# xbee_controller.net
KiCad netlist of a schematic drawn in EAGLE
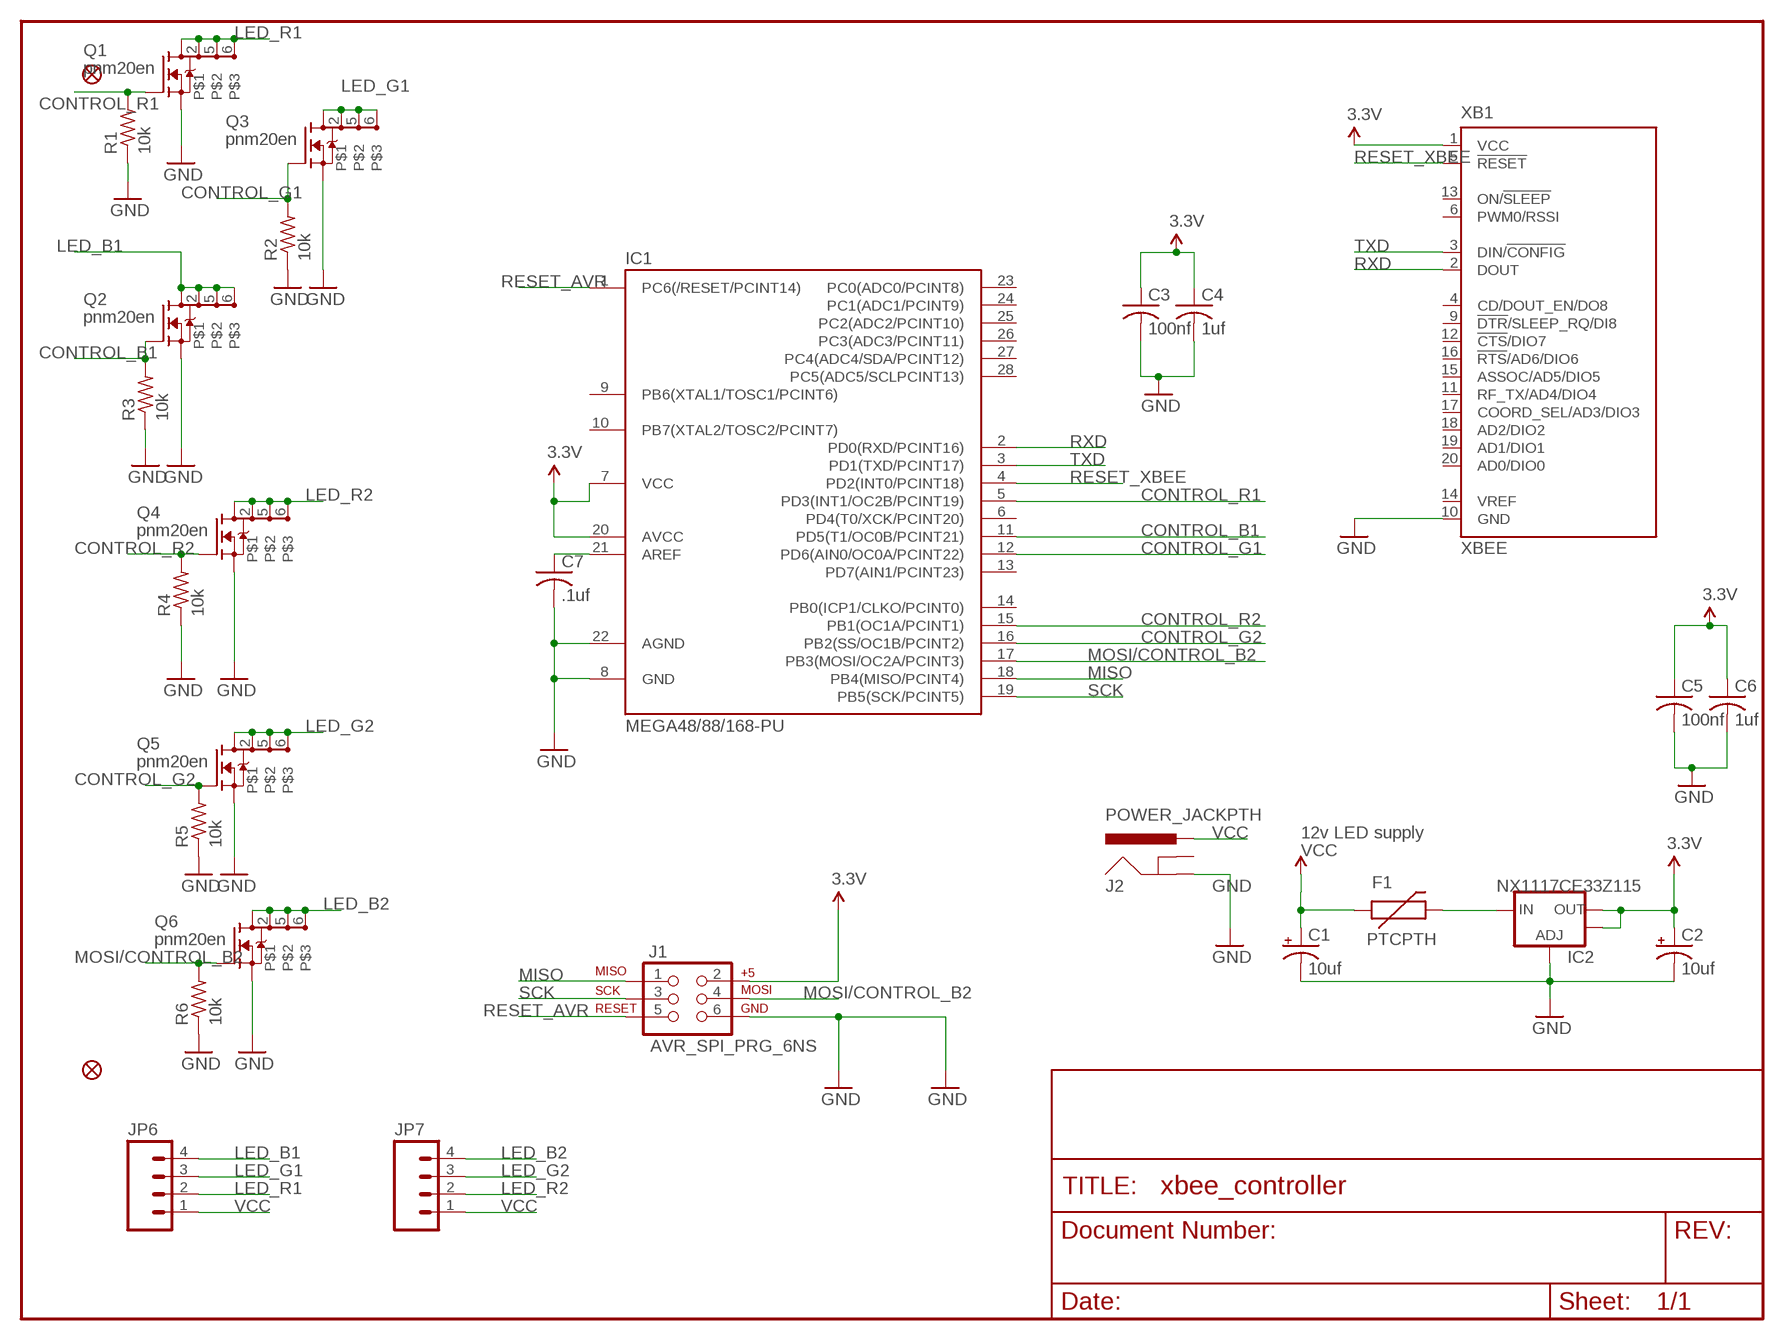
[diagram p0: schematic, sheet 1]

(export (version "E")
  (design (tool "Eeschema 10.0.6"))
  (components
    (comp (ref "C1")
      (value "10uf")
      (footprint "eagle-import:PANASONIC_A")
      (libsource (lib "eagle-import") (part "CPOL-USA"))
    )
    (comp (ref "C2")
      (value "10uf")
      (footprint "eagle-import:PANASONIC_A")
      (libsource (lib "eagle-import") (part "CPOL-USA"))
    )
    (comp (ref "C3")
      (value "100nf")
      (footprint "eagle-import:C0603")
      (libsource (lib "eagle-import") (part "C-USC0603"))
    )
    (comp (ref "C4")
      (value "1uf")
      (footprint "eagle-import:C0603")
      (libsource (lib "eagle-import") (part "C-USC0603"))
    )
    (comp (ref "C5")
      (value "100nf")
      (footprint "eagle-import:C0603")
      (libsource (lib "eagle-import") (part "C-USC0603"))
    )
    (comp (ref "C6")
      (value "1uf")
      (footprint "eagle-import:C0603")
      (libsource (lib "eagle-import") (part "C-USC0603"))
    )
    (comp (ref "C7")
      (value ".1uf")
      (footprint "eagle-import:C0603")
      (libsource (lib "eagle-import") (part "C-USC0603"))
    )
    (comp (ref "F1")
      (value "PTCPTH")
      (footprint "eagle-import:PTC")
      (libsource (lib "eagle-import") (part "PTCPTH"))
    )
    (comp (ref "IC1")
      (value "MEGA48/88/168-PU")
      (footprint "eagle-import:DIL28-3")
      (libsource (lib "eagle-import") (part "MEGA48/88/168-PU"))
    )
    (comp (ref "IC2")
      (value "NX1117CE33Z115")
      (footprint "eagle-import:SOT223")
      (libsource (lib "eagle-import") (part "V_REG_LM1117SOT223"))
    )
    (comp (ref "J1")
      (value "AVR_SPI_PRG_6NS")
      (footprint "eagle-import:2X3-NS")
      (libsource (lib "eagle-import") (part "AVR_SPI_PRG_6NS"))
    )
    (comp (ref "J2")
      (value "POWER_JACKPTH")
      (footprint "eagle-import:POWER_JACK_PTH")
      (libsource (lib "eagle-import") (part "POWER_JACKPTH"))
    )
    (comp (ref "JP2")
      (value "FIDUCIAL1.5X3")
      (footprint "eagle-import:FIDUCIAL-1.5X3")
      (libsource (lib "eagle-import") (part "FIDUCIAL1.5X3"))
    )
    (comp (ref "JP5")
      (value "FIDUCIAL1.5X3")
      (footprint "eagle-import:FIDUCIAL-1.5X3")
      (libsource (lib "eagle-import") (part "FIDUCIAL1.5X3"))
    )
    (comp (ref "JP6")
      (value "M04SCREW")
      (footprint "eagle-import:SCREWTERMINAL-3.5MM-4")
      (libsource (lib "eagle-import") (part "M04SCREW"))
    )
    (comp (ref "JP7")
      (value "M04SCREW")
      (footprint "eagle-import:SCREWTERMINAL-3.5MM-4")
      (libsource (lib "eagle-import") (part "M04SCREW"))
    )
    (comp (ref "Q1")
      (value "pnm20en")
      (footprint "eagle-import:BCR405U")
      (libsource (lib "eagle-import") (part "PMN20EN"))
    )
    (comp (ref "Q2")
      (value "pnm20en")
      (footprint "eagle-import:BCR405U")
      (libsource (lib "eagle-import") (part "PMN20EN"))
    )
    (comp (ref "Q3")
      (value "pnm20en")
      (footprint "eagle-import:BCR405U")
      (libsource (lib "eagle-import") (part "PMN20EN"))
    )
    (comp (ref "Q4")
      (value "pnm20en")
      (footprint "eagle-import:BCR405U")
      (libsource (lib "eagle-import") (part "PMN20EN"))
    )
    (comp (ref "Q5")
      (value "pnm20en")
      (footprint "eagle-import:BCR405U")
      (libsource (lib "eagle-import") (part "PMN20EN"))
    )
    (comp (ref "Q6")
      (value "pnm20en")
      (footprint "eagle-import:BCR405U")
      (libsource (lib "eagle-import") (part "PMN20EN"))
    )
    (comp (ref "R1")
      (value "10k")
      (footprint "eagle-import:R0603")
      (libsource (lib "eagle-import") (part "R-US_R0603"))
    )
    (comp (ref "R2")
      (value "10k")
      (footprint "eagle-import:R0603")
      (libsource (lib "eagle-import") (part "R-US_R0603"))
    )
    (comp (ref "R3")
      (value "10k")
      (footprint "eagle-import:R0603")
      (libsource (lib "eagle-import") (part "R-US_R0603"))
    )
    (comp (ref "R4")
      (value "10k")
      (footprint "eagle-import:R0603")
      (libsource (lib "eagle-import") (part "R-US_R0603"))
    )
    (comp (ref "R5")
      (value "10k")
      (footprint "eagle-import:R0603")
      (libsource (lib "eagle-import") (part "R-US_R0603"))
    )
    (comp (ref "R6")
      (value "10k")
      (footprint "eagle-import:R0603")
      (libsource (lib "eagle-import") (part "R-US_R0603"))
    )
    (comp (ref "XB1")
      (value "XBEE")
      (footprint "eagle-import:XBEE")
      (fields (field (name "MPN") "XBP24-Z7UIT-004"))
      (libsource (lib "eagle-import") (part "XBEE"))
    )
  )
  (nets
    (net (code "1") (name "/CONTROL_B1") (class "Default")
      (node (ref "IC1") (pin "11") (pinfunction "PD5(T1/OC0B/PCINT21)_11") (pintype "bidirectional"))
      (node (ref "Q2") (pin "3") (pinfunction "G_3") (pintype "passive"))
      (node (ref "R3") (pin "2") (pinfunction "2_2") (pintype "passive"))
    )
    (net (code "2") (name "/CONTROL_G1") (class "Default")
      (node (ref "IC1") (pin "12") (pinfunction "PD6(AIN0/OC0A/PCINT22)_12") (pintype "bidirectional"))
      (node (ref "Q3") (pin "3") (pinfunction "G_3") (pintype "passive"))
      (node (ref "R2") (pin "2") (pinfunction "2_2") (pintype "passive"))
    )
    (net (code "3") (name "/CONTROL_G2") (class "Default")
      (node (ref "IC1") (pin "16") (pinfunction "PB2(SS/OC1B/PCINT2)_16") (pintype "bidirectional"))
      (node (ref "Q5") (pin "3") (pinfunction "G_3") (pintype "passive"))
      (node (ref "R5") (pin "2") (pinfunction "2_2") (pintype "passive"))
    )
    (net (code "4") (name "/CONTROL_R1") (class "Default")
      (node (ref "IC1") (pin "5") (pinfunction "PD3(INT1/OC2B/PCINT19)_5") (pintype "bidirectional"))
      (node (ref "Q1") (pin "3") (pinfunction "G_3") (pintype "passive"))
      (node (ref "R1") (pin "2") (pinfunction "2_2") (pintype "passive"))
    )
    (net (code "5") (name "/CONTROL_R2") (class "Default")
      (node (ref "IC1") (pin "15") (pinfunction "PB1(OC1A/PCINT1)_15") (pintype "bidirectional"))
      (node (ref "Q4") (pin "3") (pinfunction "G_3") (pintype "passive"))
      (node (ref "R4") (pin "2") (pinfunction "2_2") (pintype "passive"))
    )
    (net (code "6") (name "/LED_B1") (class "Default")
      (node (ref "JP6") (pin "4") (pinfunction "4_4") (pintype "passive"))
      (node (ref "Q2") (pin "1") (pinfunction "D_1") (pintype "passive"))
      (node (ref "Q2") (pin "2") (pinfunction "P$1_2") (pintype "passive"))
      (node (ref "Q2") (pin "5") (pinfunction "P$2_5") (pintype "passive"))
      (node (ref "Q2") (pin "6") (pinfunction "P$3_6") (pintype "passive"))
    )
    (net (code "7") (name "/LED_B2") (class "Default")
      (node (ref "JP7") (pin "4") (pinfunction "4_4") (pintype "passive"))
      (node (ref "Q6") (pin "1") (pinfunction "D_1") (pintype "passive"))
      (node (ref "Q6") (pin "2") (pinfunction "P$1_2") (pintype "passive"))
      (node (ref "Q6") (pin "5") (pinfunction "P$2_5") (pintype "passive"))
      (node (ref "Q6") (pin "6") (pinfunction "P$3_6") (pintype "passive"))
    )
    (net (code "8") (name "/LED_G1") (class "Default")
      (node (ref "JP6") (pin "3") (pinfunction "3_3") (pintype "passive"))
      (node (ref "Q3") (pin "1") (pinfunction "D_1") (pintype "passive"))
      (node (ref "Q3") (pin "2") (pinfunction "P$1_2") (pintype "passive"))
      (node (ref "Q3") (pin "5") (pinfunction "P$2_5") (pintype "passive"))
      (node (ref "Q3") (pin "6") (pinfunction "P$3_6") (pintype "passive"))
    )
    (net (code "9") (name "/LED_G2") (class "Default")
      (node (ref "JP7") (pin "3") (pinfunction "3_3") (pintype "passive"))
      (node (ref "Q5") (pin "1") (pinfunction "D_1") (pintype "passive"))
      (node (ref "Q5") (pin "2") (pinfunction "P$1_2") (pintype "passive"))
      (node (ref "Q5") (pin "5") (pinfunction "P$2_5") (pintype "passive"))
      (node (ref "Q5") (pin "6") (pinfunction "P$3_6") (pintype "passive"))
    )
    (net (code "10") (name "/LED_R1") (class "Default")
      (node (ref "JP6") (pin "2") (pinfunction "2_2") (pintype "passive"))
      (node (ref "Q1") (pin "1") (pinfunction "D_1") (pintype "passive"))
      (node (ref "Q1") (pin "2") (pinfunction "P$1_2") (pintype "passive"))
      (node (ref "Q1") (pin "5") (pinfunction "P$2_5") (pintype "passive"))
      (node (ref "Q1") (pin "6") (pinfunction "P$3_6") (pintype "passive"))
    )
    (net (code "11") (name "/LED_R2") (class "Default")
      (node (ref "JP7") (pin "2") (pinfunction "2_2") (pintype "passive"))
      (node (ref "Q4") (pin "1") (pinfunction "D_1") (pintype "passive"))
      (node (ref "Q4") (pin "2") (pinfunction "P$1_2") (pintype "passive"))
      (node (ref "Q4") (pin "5") (pinfunction "P$2_5") (pintype "passive"))
      (node (ref "Q4") (pin "6") (pinfunction "P$3_6") (pintype "passive"))
    )
    (net (code "12") (name "/MISO") (class "Default")
      (node (ref "IC1") (pin "18") (pinfunction "PB4(MISO/PCINT4)_18") (pintype "bidirectional"))
      (node (ref "J1") (pin "1") (pinfunction "1_1") (pintype "passive"))
    )
    (net (code "13") (name "/MOSI{slash}CONTROL_B2") (class "Default")
      (node (ref "IC1") (pin "17") (pinfunction "PB3(MOSI/OC2A/PCINT3)_17") (pintype "bidirectional"))
      (node (ref "J1") (pin "4") (pinfunction "4_4") (pintype "passive"))
      (node (ref "Q6") (pin "3") (pinfunction "G_3") (pintype "passive"))
      (node (ref "R6") (pin "2") (pinfunction "2_2") (pintype "passive"))
    )
    (net (code "14") (name "/RESET_AVR") (class "Default")
      (node (ref "IC1") (pin "1") (pinfunction "PC6(/RESET/PCINT14)_1") (pintype "bidirectional"))
      (node (ref "J1") (pin "5") (pinfunction "5_5") (pintype "passive"))
    )
    (net (code "15") (name "/RESET_XBEE") (class "Default")
      (node (ref "IC1") (pin "4") (pinfunction "PD2(INT0/PCINT18)_4") (pintype "bidirectional"))
      (node (ref "XB1") (pin "5") (pinfunction "~{RESET}_5") (pintype "input"))
    )
    (net (code "16") (name "/RXD") (class "Default")
      (node (ref "IC1") (pin "2") (pinfunction "PD0(RXD/PCINT16)_2") (pintype "bidirectional"))
      (node (ref "XB1") (pin "2") (pinfunction "DOUT_2") (pintype "output"))
    )
    (net (code "17") (name "/SCK") (class "Default")
      (node (ref "IC1") (pin "19") (pinfunction "PB5(SCK/PCINT5)_19") (pintype "bidirectional"))
      (node (ref "J1") (pin "3") (pinfunction "3_3") (pintype "passive"))
    )
    (net (code "18") (name "/TXD") (class "Default")
      (node (ref "IC1") (pin "3") (pinfunction "PD1(TXD/PCINT17)_3") (pintype "bidirectional"))
      (node (ref "XB1") (pin "3") (pinfunction "DIN/~{CONFIG}_3") (pintype "input"))
    )
    (net (code "19") (name "3.3V") (class "Default")
      (node (ref "C2") (pin "+") (pinfunction "+_+") (pintype "passive"))
      (node (ref "C3") (pin "1") (pinfunction "1_1") (pintype "passive"))
      (node (ref "C4") (pin "1") (pinfunction "1_1") (pintype "passive"))
      (node (ref "C5") (pin "1") (pinfunction "1_1") (pintype "passive"))
      (node (ref "C6") (pin "1") (pinfunction "1_1") (pintype "passive"))
      (node (ref "IC1") (pin "20") (pinfunction "AVCC_20") (pintype "passive"))
      (node (ref "IC1") (pin "7") (pinfunction "VCC_7") (pintype "power_in"))
      (node (ref "IC2") (pin "2") (pinfunction "OUT_2") (pintype "output"))
      (node (ref "IC2") (pin "4") (pinfunction "OUT_4") (pintype "output"))
      (node (ref "J1") (pin "2") (pinfunction "2_2") (pintype "passive"))
      (node (ref "XB1") (pin "1") (pinfunction "VCC_1") (pintype "power_in"))
    )
    (net (code "20") (name "GND") (class "Default")
      (node (ref "C1") (pin "-") (pinfunction "-_-") (pintype "passive"))
      (node (ref "C2") (pin "-") (pinfunction "-_-") (pintype "passive"))
      (node (ref "C3") (pin "2") (pinfunction "2_2") (pintype "passive"))
      (node (ref "C4") (pin "2") (pinfunction "2_2") (pintype "passive"))
      (node (ref "C5") (pin "2") (pinfunction "2_2") (pintype "passive"))
      (node (ref "C6") (pin "2") (pinfunction "2_2") (pintype "passive"))
      (node (ref "C7") (pin "2") (pinfunction "2_2") (pintype "passive"))
      (node (ref "IC1") (pin "22") (pinfunction "AGND_22") (pintype "power_in"))
      (node (ref "IC1") (pin "8") (pinfunction "GND_8") (pintype "power_in"))
      (node (ref "IC2") (pin "1") (pinfunction "ADJ_1") (pintype "input"))
      (node (ref "J1") (pin "6") (pinfunction "6_6") (pintype "passive"))
      (node (ref "J2") (pin "GND") (pinfunction "GND_GND") (pintype "bidirectional"))
      (node (ref "Q1") (pin "4") (pinfunction "S_4") (pintype "passive"))
      (node (ref "Q2") (pin "4") (pinfunction "S_4") (pintype "passive"))
      (node (ref "Q3") (pin "4") (pinfunction "S_4") (pintype "passive"))
      (node (ref "Q4") (pin "4") (pinfunction "S_4") (pintype "passive"))
      (node (ref "Q5") (pin "4") (pinfunction "S_4") (pintype "passive"))
      (node (ref "Q6") (pin "4") (pinfunction "S_4") (pintype "passive"))
      (node (ref "R1") (pin "1") (pinfunction "1_1") (pintype "passive"))
      (node (ref "R2") (pin "1") (pinfunction "1_1") (pintype "passive"))
      (node (ref "R3") (pin "1") (pinfunction "1_1") (pintype "passive"))
      (node (ref "R4") (pin "1") (pinfunction "1_1") (pintype "passive"))
      (node (ref "R5") (pin "1") (pinfunction "1_1") (pintype "passive"))
      (node (ref "R6") (pin "1") (pinfunction "1_1") (pintype "passive"))
      (node (ref "XB1") (pin "10") (pinfunction "GND_10") (pintype "power_in"))
    )
    (net (code "21") (name "Net-(F1-2)") (class "Default")
      (node (ref "F1") (pin "P$2") (pinfunction "2_P$2") (pintype "bidirectional"))
      (node (ref "IC2") (pin "3") (pinfunction "IN_3") (pintype "input"))
    )
    (net (code "22") (name "Net-(IC1-AREF)") (class "Default")
      (node (ref "C7") (pin "1") (pinfunction "1_1") (pintype "passive"))
      (node (ref "IC1") (pin "21") (pinfunction "AREF_21") (pintype "passive"))
    )
    (net (code "23") (name "VCC") (class "Default")
      (node (ref "C1") (pin "+") (pinfunction "+_+") (pintype "passive"))
      (node (ref "F1") (pin "P$1") (pinfunction "1_P$1") (pintype "bidirectional"))
      (node (ref "J2") (pin "PWR") (pinfunction "PWR_PWR") (pintype "bidirectional"))
      (node (ref "JP6") (pin "1") (pinfunction "1_1") (pintype "passive"))
      (node (ref "JP7") (pin "1") (pinfunction "1_1") (pintype "passive"))
    )
    (net (code "24") (name "unconnected-(IC1-PB0(ICP1{slash}CLKO{slash}PCINT0)-Pad14)") (class "Default")
      (node (ref "IC1") (pin "14") (pinfunction "PB0(ICP1/CLKO/PCINT0)_14") (pintype "bidirectional"))
    )
    (net (code "25") (name "unconnected-(IC1-PB6(XTAL1{slash}TOSC1{slash}PCINT6)-Pad9)") (class "Default")
      (node (ref "IC1") (pin "9") (pinfunction "PB6(XTAL1/TOSC1/PCINT6)_9") (pintype "bidirectional"))
    )
    (net (code "26") (name "unconnected-(IC1-PB7(XTAL2{slash}TOSC2{slash}PCINT7)-Pad10)") (class "Default")
      (node (ref "IC1") (pin "10") (pinfunction "PB7(XTAL2/TOSC2/PCINT7)_10") (pintype "bidirectional"))
    )
    (net (code "27") (name "unconnected-(IC1-PC0(ADC0{slash}PCINT8)-Pad23)") (class "Default")
      (node (ref "IC1") (pin "23") (pinfunction "PC0(ADC0/PCINT8)_23") (pintype "bidirectional"))
    )
    (net (code "28") (name "unconnected-(IC1-PC1(ADC1{slash}PCINT9)-Pad24)") (class "Default")
      (node (ref "IC1") (pin "24") (pinfunction "PC1(ADC1/PCINT9)_24") (pintype "bidirectional"))
    )
    (net (code "29") (name "unconnected-(IC1-PC2(ADC2{slash}PCINT10)-Pad25)") (class "Default")
      (node (ref "IC1") (pin "25") (pinfunction "PC2(ADC2/PCINT10)_25") (pintype "bidirectional"))
    )
    (net (code "30") (name "unconnected-(IC1-PC3(ADC3{slash}PCINT11)-Pad26)") (class "Default")
      (node (ref "IC1") (pin "26") (pinfunction "PC3(ADC3/PCINT11)_26") (pintype "bidirectional"))
    )
    (net (code "31") (name "unconnected-(IC1-PC4(ADC4{slash}SDA{slash}PCINT12)-Pad27)") (class "Default")
      (node (ref "IC1") (pin "27") (pinfunction "PC4(ADC4/SDA/PCINT12)_27") (pintype "bidirectional"))
    )
    (net (code "32") (name "unconnected-(IC1-PC5(ADC5{slash}SCLPCINT13)-Pad28)") (class "Default")
      (node (ref "IC1") (pin "28") (pinfunction "PC5(ADC5/SCLPCINT13)_28") (pintype "bidirectional"))
    )
    (net (code "33") (name "unconnected-(IC1-PD4(T0{slash}XCK{slash}PCINT20)-Pad6)") (class "Default")
      (node (ref "IC1") (pin "6") (pinfunction "PD4(T0/XCK/PCINT20)_6") (pintype "bidirectional"))
    )
    (net (code "34") (name "unconnected-(IC1-PD7(AIN1{slash}PCINT23)-Pad13)") (class "Default")
      (node (ref "IC1") (pin "13") (pinfunction "PD7(AIN1/PCINT23)_13") (pintype "bidirectional"))
    )
    (net (code "35") (name "unconnected-(J2-PadGNDBREAK)") (class "Default")
      (node (ref "J2") (pin "GNDBREAK") (pinfunction "GNDBREAK_GNDBREAK") (pintype "bidirectional"))
    )
    (net (code "36") (name "unconnected-(XB1-AD0{slash}DIO0-Pad20)") (class "Default")
      (node (ref "XB1") (pin "20") (pinfunction "AD0/DIO0_20") (pintype "bidirectional"))
    )
    (net (code "37") (name "unconnected-(XB1-AD1{slash}DIO1-Pad19)") (class "Default")
      (node (ref "XB1") (pin "19") (pinfunction "AD1/DIO1_19") (pintype "bidirectional"))
    )
    (net (code "38") (name "unconnected-(XB1-AD2{slash}DIO2-Pad18)") (class "Default")
      (node (ref "XB1") (pin "18") (pinfunction "AD2/DIO2_18") (pintype "bidirectional"))
    )
    (net (code "39") (name "unconnected-(XB1-ASSOC{slash}AD5{slash}DIO5-Pad15)") (class "Default")
      (node (ref "XB1") (pin "15") (pinfunction "ASSOC/AD5/DIO5_15") (pintype "bidirectional"))
    )
    (net (code "40") (name "unconnected-(XB1-CD{slash}DOUT_EN{slash}DO8-Pad4)") (class "Default")
      (node (ref "XB1") (pin "4") (pinfunction "CD/DOUT_EN/DO8_4") (pintype "output"))
    )
    (net (code "41") (name "unconnected-(XB1-COORD_SEL{slash}AD3{slash}DIO3-Pad17)") (class "Default")
      (node (ref "XB1") (pin "17") (pinfunction "COORD_SEL/AD3/DIO3_17") (pintype "bidirectional"))
    )
    (net (code "42") (name "unconnected-(XB1-ON{slash}~{SLEEP}-Pad13)") (class "Default")
      (node (ref "XB1") (pin "13") (pinfunction "ON/~{SLEEP}_13") (pintype "output"))
    )
    (net (code "43") (name "unconnected-(XB1-PWM0{slash}RSSI-Pad6)") (class "Default")
      (node (ref "XB1") (pin "6") (pinfunction "PWM0/RSSI_6") (pintype "output"))
    )
    (net (code "44") (name "unconnected-(XB1-RF_TX{slash}AD4{slash}DIO4-Pad11)") (class "Default")
      (node (ref "XB1") (pin "11") (pinfunction "RF_TX/AD4/DIO4_11") (pintype "bidirectional"))
    )
    (net (code "45") (name "unconnected-(XB1-VREF-Pad14)") (class "Default")
      (node (ref "XB1") (pin "14") (pinfunction "VREF_14") (pintype "input"))
    )
    (net (code "46") (name "unconnected-(XB1-~{CTS}{slash}DIO7-Pad12)") (class "Default")
      (node (ref "XB1") (pin "12") (pinfunction "~{CTS}/DIO7_12") (pintype "bidirectional"))
    )
    (net (code "47") (name "unconnected-(XB1-~{DTR}{slash}SLEEP_RQ{slash}DI8-Pad9)") (class "Default")
      (node (ref "XB1") (pin "9") (pinfunction "~{DTR}/SLEEP_RQ/DI8_9") (pintype "bidirectional"))
    )
    (net (code "48") (name "unconnected-(XB1-~{RTS}{slash}AD6{slash}DIO6-Pad16)") (class "Default")
      (node (ref "XB1") (pin "16") (pinfunction "~{RTS}/AD6/DIO6_16") (pintype "bidirectional"))
    )
  )
)
